# Main.net
KiCad netlist of a schematic drawn in Altium Designer
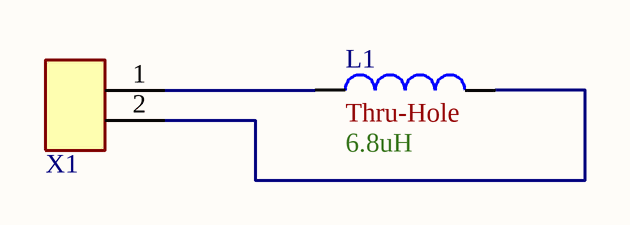
[diagram p0: Main.SchDoc]

(export (version "E")
  (design (tool "Eeschema 10.0.6"))
  (components
    (comp (ref "L1")
      (value "[6.8uH] Thru-Hole 47.5A 1.2mOhm")
      (footprint "[6.8uH] Thru-Hole 47.5A 1.2mOhm")
      (description "B82559A5682A033")
      (fields (field (name "PACKAGE") "Thru-Hole") (field (name "INDUCTANCE") "6.8uH"))
      (libsource (lib "Inductors") (part "[6.8uH] Thru-Hole 47.5A 1.2mOhm"))
    )
    (comp (ref "X1")
      (value "2pin Screw Terminal")
      (footprint "[Screw Terminal] 2pin 5mm")
      (description "TB002-500-02BE")
      (libsource (lib "Connectors") (part "[Screw Terminal] 2pin"))
    )
  )
  (nets
    (net (code "1") (name "Net-(L1-Pad1)") (class "Default")
      (node (ref "L1") (pin "1") (pinfunction "1_1") (pintype "passive"))
      (node (ref "X1") (pin "1") (pintype "power_in"))
    )
    (net (code "2") (name "Net-(L1-Pad2)") (class "Default")
      (node (ref "L1") (pin "2") (pinfunction "2_2") (pintype "passive"))
      (node (ref "X1") (pin "2") (pintype "power_in"))
    )
  )
)
